# SX1308_GTW_e381v02c_SX1308_part.net
KiCad netlist of a schematic drawn in Altium Designer
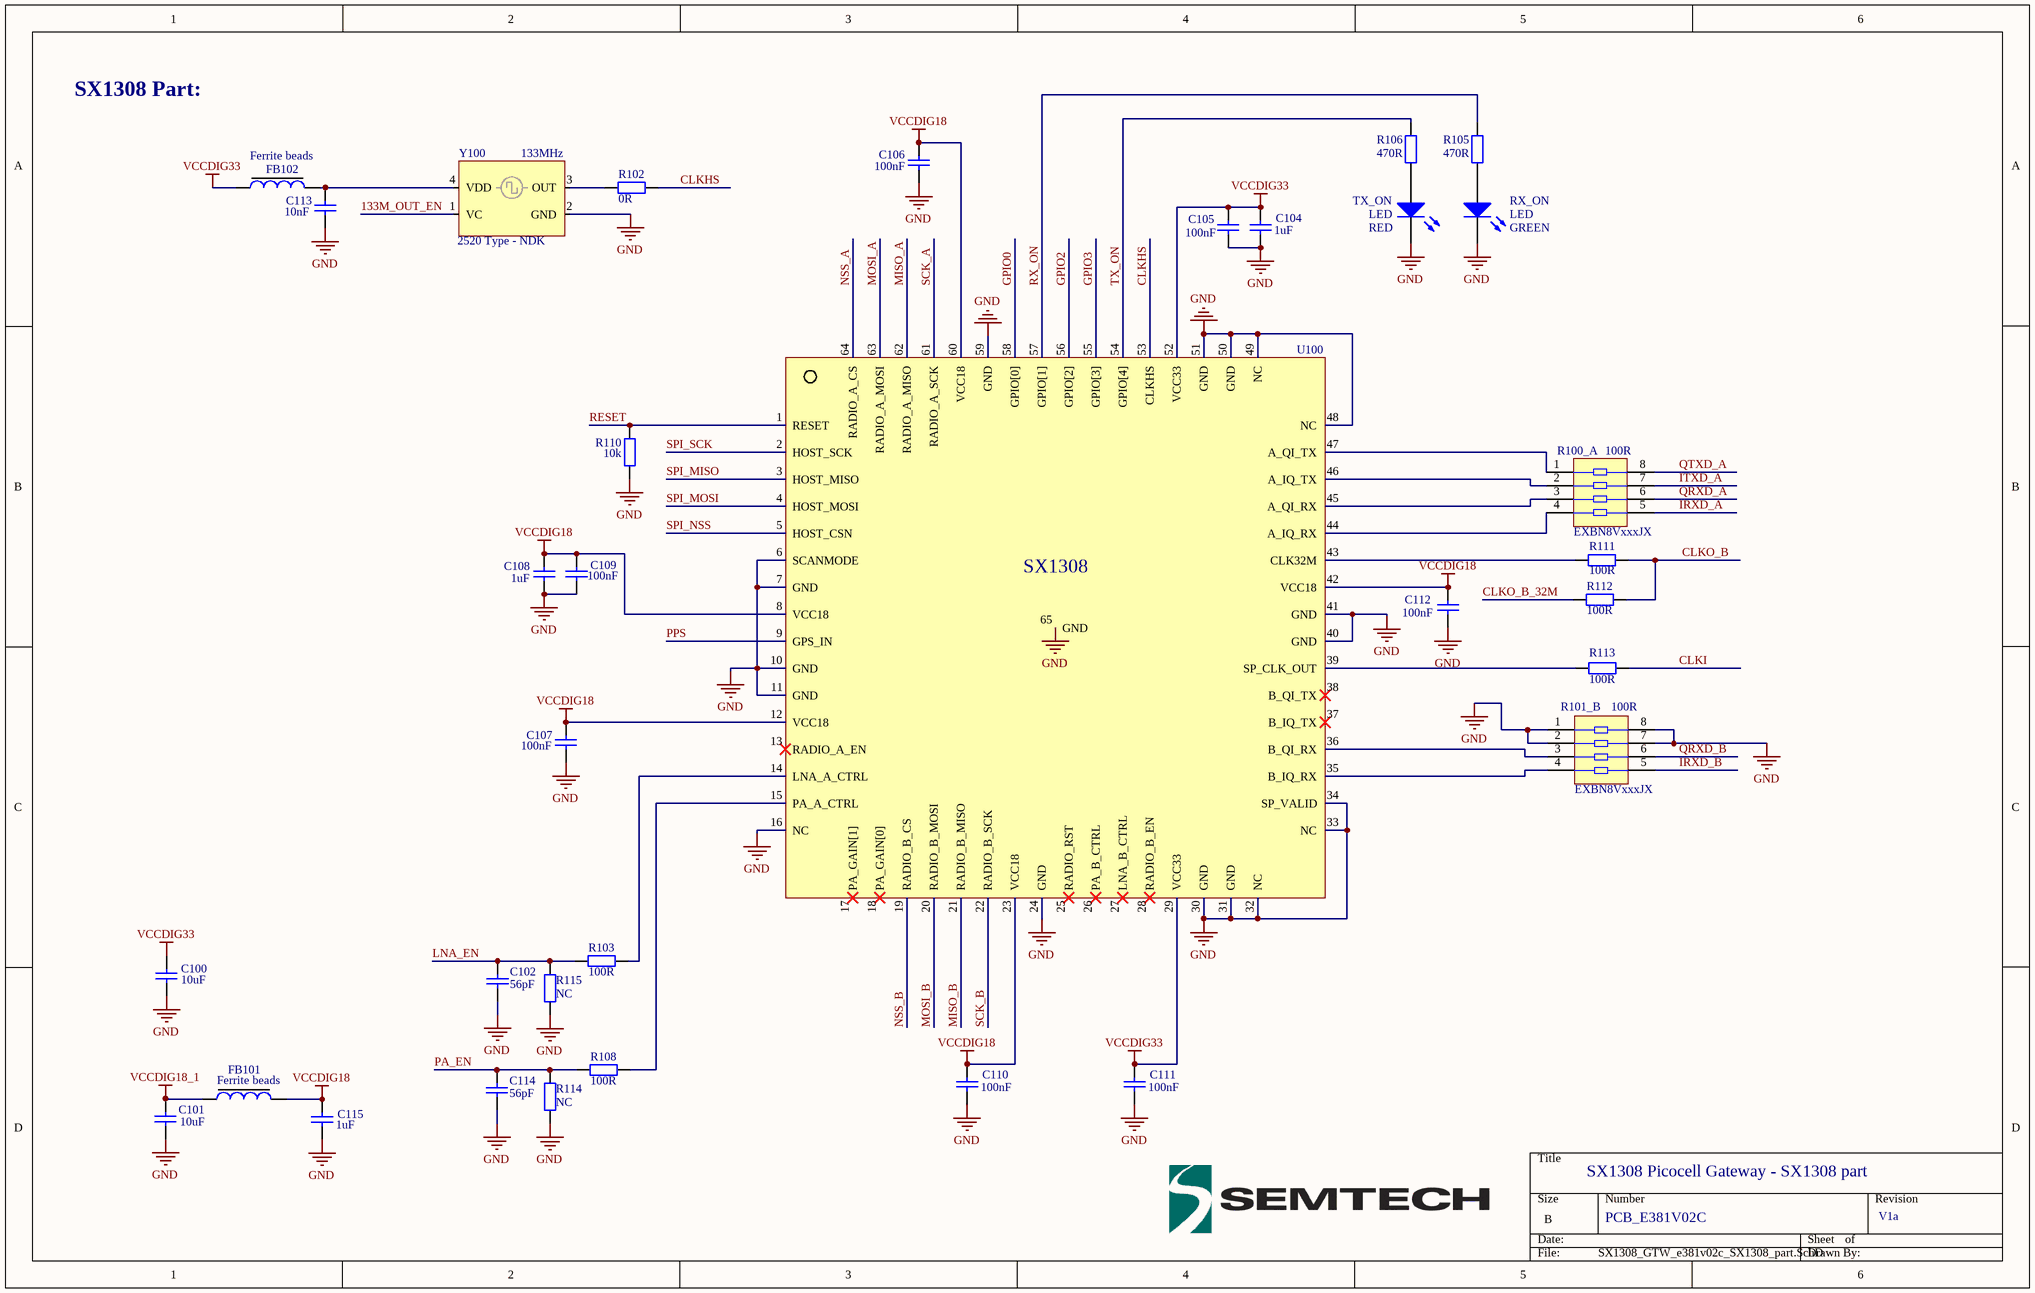
[diagram p0: SX1308_GTW_e381v02c_SX1308_part.SchDoc]

(export (version "E")
  (design (tool "Eeschema 10.0.6"))
  (components
    (comp (ref "C100")
      (value "10uF")
      (footprint "rlc_805_smd")
      (description "Capacitor SMD")
      (fields (field (name "Comment") "Cap") (field (name "PUBLISHER") "Altium Limited"))
      (libsource (lib "SX1308_GTW_e381v02c") (part "Cap"))
    )
    (comp (ref "C101")
      (value "10uF")
      (footprint "rlc_805_smd")
      (description "Capacitor SMD")
      (fields (field (name "Comment") "Cap") (field (name "PUBLISHER") "Altium Limited"))
      (libsource (lib "SX1308_GTW_e381v02c") (part "Cap"))
    )
    (comp (ref "C102")
      (value "56pF")
      (footprint "rlc_402_smd")
      (description "Capacitor SMD")
      (fields (field (name "Comment") "Cap") (field (name "PUBLISHER") "Altium Limited"))
      (libsource (lib "SX1308_GTW_e381v02c") (part "Cap"))
    )
    (comp (ref "C104")
      (value "1uF")
      (footprint "rlc_603_smd")
      (description "Capacitor SMD")
      (fields (field (name "Comment") "Cap") (field (name "PUBLISHER") "Altium Limited"))
      (libsource (lib "SX1308_GTW_e381v02c") (part "Cap"))
    )
    (comp (ref "C105")
      (value "100nF")
      (footprint "rlc_402_smd")
      (description "Capacitor SMD")
      (fields (field (name "Comment") "Cap") (field (name "PUBLISHER") "Altium Limited"))
      (libsource (lib "SX1308_GTW_e381v02c") (part "Cap"))
    )
    (comp (ref "C106")
      (value "100nF")
      (footprint "rlc_402_smd")
      (description "Capacitor SMD")
      (fields (field (name "Comment") "Cap") (field (name "PUBLISHER") "Altium Limited"))
      (libsource (lib "SX1308_GTW_e381v02c") (part "Cap"))
    )
    (comp (ref "C107")
      (value "100nF")
      (footprint "rlc_402_smd")
      (description "Capacitor SMD")
      (fields (field (name "Comment") "Cap") (field (name "PUBLISHER") "Altium Limited"))
      (libsource (lib "SX1308_GTW_e381v02c") (part "Cap"))
    )
    (comp (ref "C108")
      (value "1uF")
      (footprint "rlc_603_smd")
      (description "Capacitor SMD")
      (fields (field (name "Comment") "Cap") (field (name "PUBLISHER") "Altium Limited"))
      (libsource (lib "SX1308_GTW_e381v02c") (part "Cap"))
    )
    (comp (ref "C109")
      (value "100nF")
      (footprint "rlc_402_smd")
      (description "Capacitor SMD")
      (fields (field (name "Comment") "Cap") (field (name "PUBLISHER") "Altium Limited"))
      (libsource (lib "SX1308_GTW_e381v02c") (part "Cap"))
    )
    (comp (ref "C110")
      (value "100nF")
      (footprint "rlc_402_smd")
      (description "Capacitor SMD")
      (fields (field (name "Comment") "Cap") (field (name "PUBLISHER") "Altium Limited"))
      (libsource (lib "SX1308_GTW_e381v02c") (part "Cap"))
    )
    (comp (ref "C111")
      (value "100nF")
      (footprint "rlc_402_smd")
      (description "Capacitor SMD")
      (fields (field (name "Comment") "Cap") (field (name "PUBLISHER") "Altium Limited"))
      (libsource (lib "SX1308_GTW_e381v02c") (part "Cap"))
    )
    (comp (ref "C112")
      (value "100nF")
      (footprint "rlc_402_smd")
      (description "Capacitor SMD")
      (fields (field (name "Comment") "Cap") (field (name "PUBLISHER") "Altium Limited"))
      (libsource (lib "SX1308_GTW_e381v02c") (part "Cap"))
    )
    (comp (ref "C113")
      (value "10nF")
      (footprint "rlc_402_smd")
      (description "Capacitor SMD")
      (fields (field (name "Comment") "Cap") (field (name "PUBLISHER") "Altium Limited"))
      (libsource (lib "SX1308_GTW_e381v02c") (part "Cap"))
    )
    (comp (ref "C114")
      (value "56pF")
      (footprint "rlc_402_smd")
      (description "Capacitor SMD")
      (fields (field (name "Comment") "Cap") (field (name "PUBLISHER") "Altium Limited"))
      (libsource (lib "SX1308_GTW_e381v02c") (part "Cap"))
    )
    (comp (ref "C115")
      (value "1uF")
      (footprint "rlc_603_smd")
      (description "Capacitor SMD")
      (fields (field (name "Comment") "Cap") (field (name "PUBLISHER") "Altium Limited"))
      (libsource (lib "SX1308_GTW_e381v02c") (part "Cap"))
    )
    (comp (ref "FB101")
      (value "Ferrite beads")
      (footprint "rlc_402_smd")
      (libsource (lib "SX1308_GTW_e381v02c") (part "Ferrite beads"))
    )
    (comp (ref "FB102")
      (value "Ferrite beads")
      (footprint "rlc_402_smd")
      (libsource (lib "SX1308_GTW_e381v02c") (part "Ferrite beads"))
    )
    (comp (ref "R100_A")
      (value "EXBN8VxxxJX")
      (footprint "EXB28V")
      (description "Mini-Flat Package, Isolated Resistor Network, 0.031 W/resistor")
      (fields (field (name "ALTIUM_VALUE") "100R"))
      (libsource (lib "SX1308_GTW_e381v02c") (part "EXBN8VxxxJX"))
    )
    (comp (ref "R101_B")
      (value "EXBN8VxxxJX")
      (footprint "EXB28V")
      (description "Mini-Flat Package, Isolated Resistor Network, 0.031 W/resistor")
      (fields (field (name "ALTIUM_VALUE") "100R"))
      (libsource (lib "SX1308_GTW_e381v02c") (part "EXBN8VxxxJX"))
    )
    (comp (ref "R102")
      (value "0R")
      (footprint "rlc_402_smd")
      (description "Resistor SMD - IEC symbol version")
      (fields (field (name "Comment") "Resistor"))
      (libsource (lib "SX1308_GTW_e381v02c") (part "Resistor"))
    )
    (comp (ref "R103")
      (value "100R")
      (footprint "rlc_402_smd")
      (description "Resistor SMD - IEC symbol version")
      (fields (field (name "Comment") "Resistor"))
      (libsource (lib "SX1308_GTW_e381v02c") (part "Resistor"))
    )
    (comp (ref "R105")
      (value "470R")
      (footprint "rlc_402_smd")
      (description "Resistor SMD - IEC symbol version")
      (fields (field (name "Comment") "Resistor"))
      (libsource (lib "") (part "Resistor_2"))
    )
    (comp (ref "R106")
      (value "470R")
      (footprint "rlc_402_smd")
      (description "Resistor SMD - IEC symbol version")
      (fields (field (name "Comment") "Resistor"))
      (libsource (lib "") (part "Resistor_2"))
    )
    (comp (ref "R108")
      (value "100R")
      (footprint "rlc_402_smd")
      (description "Resistor SMD - IEC symbol version")
      (fields (field (name "Comment") "Resistor"))
      (libsource (lib "SX1308_GTW_e381v02c") (part "Resistor"))
    )
    (comp (ref "R110")
      (value "10k")
      (footprint "rlc_402_smd")
      (description "Resistor SMD - IEC symbol version")
      (fields (field (name "Comment") "Resistor"))
      (libsource (lib "") (part "Resistor_2"))
    )
    (comp (ref "R111")
      (value "100R")
      (footprint "rlc_402_smd")
      (description "Resistor SMD - IEC symbol version")
      (fields (field (name "Comment") "Resistor"))
      (libsource (lib "") (part "Resistor_1"))
    )
    (comp (ref "R112")
      (value "100R")
      (footprint "rlc_402_smd")
      (description "Resistor SMD - IEC symbol version")
      (fields (field (name "Comment") "Resistor"))
      (libsource (lib "") (part "Resistor_1"))
    )
    (comp (ref "R113")
      (value "100R")
      (footprint "rlc_402_smd")
      (description "Resistor SMD - IEC symbol version")
      (fields (field (name "Comment") "Resistor"))
      (libsource (lib "") (part "Resistor_1"))
    )
    (comp (ref "R114")
      (value "NC")
      (footprint "rlc_402_smd")
      (description "Resistor SMD - IEC symbol version")
      (fields (field (name "Comment") "Resistor"))
      (libsource (lib "") (part "Resistor_3"))
    )
    (comp (ref "R115")
      (value "NC")
      (footprint "rlc_402_smd")
      (description "Resistor SMD - IEC symbol version")
      (fields (field (name "Comment") "Resistor"))
      (libsource (lib "") (part "Resistor_3"))
    )
    (comp (ref "RX_ON")
      (value "LED")
      (footprint "CD3224")
      (fields (field (name "TYPE") "GREEN"))
      (libsource (lib "SX1308_GTW_e381v02c") (part "LED"))
    )
    (comp (ref "TX_ON")
      (value "LED")
      (footprint "CD3224")
      (fields (field (name "TYPE") "RED"))
      (libsource (lib "SX1308_GTW_e381v02c") (part "LED"))
    )
    (comp (ref "U100")
      (value "SX1308")
      (footprint "vqfn64_9x9mm")
      (libsource (lib "SX1308_GTW_e381v02c") (part "SX1301"))
    )
    (comp (ref "Y100")
      (value "2520 Type - NDK")
      (footprint "TCXO 2.5x2.0mm")
      (description "VCTCXO")
      (fields (field (name "ALTIUM_VALUE") "133MHz"))
      (libsource (lib "SX1308_GTW_e381v02c") (part "VCTCXO"))
    )
  )
  (nets
    (net (code "1") (name "/133M_OUT_EN") (class "Default")
      (node (ref "Y100") (pin "1") (pinfunction "VC_1") (pintype "passive"))
    )
    (net (code "2") (name "/CLKHS") (class "Default")
      (node (ref "R102") (pin "1") (pinfunction "1_1") (pintype "passive"))
      (node (ref "U100") (pin "53") (pinfunction "CLKHS_53") (pintype "passive"))
    )
    (net (code "3") (name "/CLKI") (class "Default")
      (node (ref "R113") (pin "2") (pinfunction "2_2") (pintype "passive"))
    )
    (net (code "4") (name "/CLKO_B") (class "Default")
      (node (ref "R111") (pin "2") (pinfunction "2_2") (pintype "passive"))
      (node (ref "R112") (pin "2") (pinfunction "2_2") (pintype "passive"))
    )
    (net (code "5") (name "/CLKO_B_32M") (class "Default")
      (node (ref "R112") (pin "1") (pinfunction "1_1") (pintype "passive"))
    )
    (net (code "6") (name "/GPIO0") (class "Default")
      (node (ref "U100") (pin "58") (pinfunction "GPIO[0]_58") (pintype "passive"))
    )
    (net (code "7") (name "/GPIO2") (class "Default")
      (node (ref "U100") (pin "56") (pinfunction "GPIO[2]_56") (pintype "passive"))
    )
    (net (code "8") (name "/GPIO3") (class "Default")
      (node (ref "U100") (pin "55") (pinfunction "GPIO[3]_55") (pintype "passive"))
    )
    (net (code "9") (name "/IRXD_A") (class "Default")
      (node (ref "R100_A") (pin "5") (pinfunction "5_5") (pintype "passive"))
    )
    (net (code "10") (name "/IRXD_B") (class "Default")
      (node (ref "R101_B") (pin "5") (pinfunction "5_5") (pintype "passive"))
    )
    (net (code "11") (name "/ITXD_A") (class "Default")
      (node (ref "R100_A") (pin "7") (pinfunction "7_7") (pintype "passive"))
    )
    (net (code "12") (name "/LNA_EN") (class "Default")
      (node (ref "C102") (pin "2") (pinfunction "2_2") (pintype "passive"))
      (node (ref "R103") (pin "2") (pinfunction "2_2") (pintype "passive"))
      (node (ref "R115") (pin "1") (pinfunction "1_1") (pintype "passive"))
    )
    (net (code "13") (name "/MISO_A") (class "Default")
      (node (ref "U100") (pin "62") (pinfunction "RADIO_A_MISO_62") (pintype "passive"))
    )
    (net (code "14") (name "/MISO_B") (class "Default")
      (node (ref "U100") (pin "21") (pinfunction "RADIO_B_MISO_21") (pintype "passive"))
    )
    (net (code "15") (name "/MOSI_A") (class "Default")
      (node (ref "U100") (pin "63") (pinfunction "RADIO_A_MOSI_63") (pintype "passive"))
    )
    (net (code "16") (name "/MOSI_B") (class "Default")
      (node (ref "U100") (pin "20") (pinfunction "RADIO_B_MOSI_20") (pintype "passive"))
    )
    (net (code "17") (name "/NSS_A") (class "Default")
      (node (ref "U100") (pin "64") (pinfunction "RADIO_A_CS_64") (pintype "passive"))
    )
    (net (code "18") (name "/NSS_B") (class "Default")
      (node (ref "U100") (pin "19") (pinfunction "RADIO_B_CS_19") (pintype "passive"))
    )
    (net (code "19") (name "/PA_EN") (class "Default")
      (node (ref "C114") (pin "2") (pinfunction "2_2") (pintype "passive"))
      (node (ref "R108") (pin "2") (pinfunction "2_2") (pintype "passive"))
      (node (ref "R114") (pin "1") (pinfunction "1_1") (pintype "passive"))
    )
    (net (code "20") (name "/PPS") (class "Default")
      (node (ref "U100") (pin "9") (pinfunction "GPS_IN_9") (pintype "passive"))
    )
    (net (code "21") (name "/QRXD_A") (class "Default")
      (node (ref "R100_A") (pin "6") (pinfunction "6_6") (pintype "passive"))
    )
    (net (code "22") (name "/QRXD_B") (class "Default")
      (node (ref "R101_B") (pin "6") (pinfunction "6_6") (pintype "passive"))
    )
    (net (code "23") (name "/QTXD_A") (class "Default")
      (node (ref "R100_A") (pin "8") (pinfunction "8_8") (pintype "passive"))
    )
    (net (code "24") (name "/RESET") (class "Default")
      (node (ref "R110") (pin "2") (pinfunction "2_2") (pintype "passive"))
      (node (ref "U100") (pin "1") (pinfunction "RESET_1") (pintype "passive"))
    )
    (net (code "25") (name "/RX_ON") (class "Default")
      (node (ref "R105") (pin "2") (pinfunction "2_2") (pintype "passive"))
      (node (ref "U100") (pin "57") (pinfunction "GPIO[1]_57") (pintype "passive"))
    )
    (net (code "26") (name "/SCK_A") (class "Default")
      (node (ref "U100") (pin "61") (pinfunction "RADIO_A_SCK_61") (pintype "passive"))
    )
    (net (code "27") (name "/SCK_B") (class "Default")
      (node (ref "U100") (pin "22") (pinfunction "RADIO_B_SCK_22") (pintype "passive"))
    )
    (net (code "28") (name "/SPI_MISO") (class "Default")
      (node (ref "U100") (pin "3") (pinfunction "HOST_MISO_3") (pintype "passive"))
    )
    (net (code "29") (name "/SPI_MOSI") (class "Default")
      (node (ref "U100") (pin "4") (pinfunction "HOST_MOSI_4") (pintype "passive"))
    )
    (net (code "30") (name "/SPI_NSS") (class "Default")
      (node (ref "U100") (pin "5") (pinfunction "HOST_CSN_5") (pintype "passive"))
    )
    (net (code "31") (name "/SPI_SCK") (class "Default")
      (node (ref "U100") (pin "2") (pinfunction "HOST_SCK_2") (pintype "passive"))
    )
    (net (code "32") (name "/TX_ON") (class "Default")
      (node (ref "R106") (pin "2") (pinfunction "2_2") (pintype "passive"))
      (node (ref "U100") (pin "54") (pinfunction "GPIO[4]_54") (pintype "passive"))
    )
    (net (code "33") (name "GND") (class "Default")
      (node (ref "C100") (pin "1") (pinfunction "1_1") (pintype "passive"))
      (node (ref "C101") (pin "1") (pinfunction "1_1") (pintype "passive"))
      (node (ref "C102") (pin "1") (pinfunction "1_1") (pintype "passive"))
      (node (ref "C104") (pin "1") (pinfunction "1_1") (pintype "passive"))
      (node (ref "C105") (pin "1") (pinfunction "1_1") (pintype "passive"))
      (node (ref "C106") (pin "1") (pinfunction "1_1") (pintype "passive"))
      (node (ref "C107") (pin "1") (pinfunction "1_1") (pintype "passive"))
      (node (ref "C108") (pin "1") (pinfunction "1_1") (pintype "passive"))
      (node (ref "C109") (pin "1") (pinfunction "1_1") (pintype "passive"))
      (node (ref "C110") (pin "1") (pinfunction "1_1") (pintype "passive"))
      (node (ref "C111") (pin "1") (pinfunction "1_1") (pintype "passive"))
      (node (ref "C112") (pin "1") (pinfunction "1_1") (pintype "passive"))
      (node (ref "C113") (pin "1") (pinfunction "1_1") (pintype "passive"))
      (node (ref "C114") (pin "1") (pinfunction "1_1") (pintype "passive"))
      (node (ref "C115") (pin "2") (pinfunction "2_2") (pintype "passive"))
      (node (ref "R101_B") (pin "1") (pinfunction "1_1") (pintype "passive"))
      (node (ref "R101_B") (pin "2") (pinfunction "2_2") (pintype "passive"))
      (node (ref "R101_B") (pin "7") (pinfunction "7_7") (pintype "passive"))
      (node (ref "R101_B") (pin "8") (pinfunction "8_8") (pintype "passive"))
      (node (ref "R110") (pin "1") (pinfunction "1_1") (pintype "passive"))
      (node (ref "R114") (pin "2") (pinfunction "2_2") (pintype "passive"))
      (node (ref "R115") (pin "2") (pinfunction "2_2") (pintype "passive"))
      (node (ref "RX_ON") (pin "2") (pinfunction "K_2") (pintype "passive"))
      (node (ref "TX_ON") (pin "2") (pinfunction "K_2") (pintype "passive"))
      (node (ref "U100") (pin "10") (pinfunction "GND_10") (pintype "passive"))
      (node (ref "U100") (pin "11") (pinfunction "GND_11") (pintype "passive"))
      (node (ref "U100") (pin "16") (pinfunction "NC_16") (pintype "passive"))
      (node (ref "U100") (pin "24") (pinfunction "GND_24") (pintype "passive"))
      (node (ref "U100") (pin "30") (pinfunction "GND_30") (pintype "passive"))
      (node (ref "U100") (pin "31") (pinfunction "GND_31") (pintype "passive"))
      (node (ref "U100") (pin "32") (pinfunction "NC_32") (pintype "passive"))
      (node (ref "U100") (pin "33") (pinfunction "NC_33") (pintype "passive"))
      (node (ref "U100") (pin "34") (pinfunction "SP_VALID_34") (pintype "passive"))
      (node (ref "U100") (pin "40") (pinfunction "GND_40") (pintype "passive"))
      (node (ref "U100") (pin "41") (pinfunction "GND_41") (pintype "passive"))
      (node (ref "U100") (pin "48") (pinfunction "NC_48") (pintype "passive"))
      (node (ref "U100") (pin "49") (pinfunction "NC_49") (pintype "passive"))
      (node (ref "U100") (pin "50") (pinfunction "GND_50") (pintype "passive"))
      (node (ref "U100") (pin "51") (pinfunction "GND_51") (pintype "passive"))
      (node (ref "U100") (pin "59") (pinfunction "GND_59") (pintype "passive"))
      (node (ref "U100") (pin "6") (pinfunction "SCANMODE_6") (pintype "passive"))
      (node (ref "U100") (pin "65") (pinfunction "GND_65") (pintype "passive"))
      (node (ref "U100") (pin "7") (pinfunction "GND_7") (pintype "passive"))
      (node (ref "Y100") (pin "2") (pinfunction "GND_2") (pintype "passive"))
    )
    (net (code "34") (name "Net-(RX_ON-A)") (class "Default")
      (node (ref "R105") (pin "1") (pinfunction "1_1") (pintype "passive"))
      (node (ref "RX_ON") (pin "1") (pinfunction "A_1") (pintype "passive"))
    )
    (net (code "35") (name "Net-(TX_ON-A)") (class "Default")
      (node (ref "R106") (pin "1") (pinfunction "1_1") (pintype "passive"))
      (node (ref "TX_ON") (pin "1") (pinfunction "A_1") (pintype "passive"))
    )
    (net (code "36") (name "Net-(U100-A_IQ_RX)") (class "Default")
      (node (ref "R100_A") (pin "4") (pinfunction "4_4") (pintype "passive"))
      (node (ref "U100") (pin "44") (pinfunction "A_IQ_RX_44") (pintype "passive"))
    )
    (net (code "37") (name "Net-(U100-A_IQ_TX)") (class "Default")
      (node (ref "R100_A") (pin "2") (pinfunction "2_2") (pintype "passive"))
      (node (ref "U100") (pin "46") (pinfunction "A_IQ_TX_46") (pintype "passive"))
    )
    (net (code "38") (name "Net-(U100-A_QI_RX)") (class "Default")
      (node (ref "R100_A") (pin "3") (pinfunction "3_3") (pintype "passive"))
      (node (ref "U100") (pin "45") (pinfunction "A_QI_RX_45") (pintype "passive"))
    )
    (net (code "39") (name "Net-(U100-A_QI_TX)") (class "Default")
      (node (ref "R100_A") (pin "1") (pinfunction "1_1") (pintype "passive"))
      (node (ref "U100") (pin "47") (pinfunction "A_QI_TX_47") (pintype "passive"))
    )
    (net (code "40") (name "Net-(U100-B_IQ_RX)") (class "Default")
      (node (ref "R101_B") (pin "4") (pinfunction "4_4") (pintype "passive"))
      (node (ref "U100") (pin "35") (pinfunction "B_IQ_RX_35") (pintype "passive"))
    )
    (net (code "41") (name "Net-(U100-B_QI_RX)") (class "Default")
      (node (ref "R101_B") (pin "3") (pinfunction "3_3") (pintype "passive"))
      (node (ref "U100") (pin "36") (pinfunction "B_QI_RX_36") (pintype "passive"))
    )
    (net (code "42") (name "Net-(U100-CLK32M)") (class "Default")
      (node (ref "R111") (pin "1") (pinfunction "1_1") (pintype "passive"))
      (node (ref "U100") (pin "43") (pinfunction "CLK32M_43") (pintype "passive"))
    )
    (net (code "43") (name "Net-(U100-LNA_A_CTRL)") (class "Default")
      (node (ref "R103") (pin "1") (pinfunction "1_1") (pintype "passive"))
      (node (ref "U100") (pin "14") (pinfunction "LNA_A_CTRL_14") (pintype "passive"))
    )
    (net (code "44") (name "Net-(U100-PA_A_CTRL)") (class "Default")
      (node (ref "R108") (pin "1") (pinfunction "1_1") (pintype "passive"))
      (node (ref "U100") (pin "15") (pinfunction "PA_A_CTRL_15") (pintype "passive"))
    )
    (net (code "45") (name "Net-(U100-SP_CLK_OUT)") (class "Default")
      (node (ref "R113") (pin "1") (pinfunction "1_1") (pintype "passive"))
      (node (ref "U100") (pin "39") (pinfunction "SP_CLK_OUT_39") (pintype "passive"))
    )
    (net (code "46") (name "Net-(Y100-OUT)") (class "Default")
      (node (ref "R102") (pin "2") (pinfunction "2_2") (pintype "passive"))
      (node (ref "Y100") (pin "3") (pinfunction "OUT_3") (pintype "passive"))
    )
    (net (code "47") (name "Net-(Y100-VDD)") (class "Default")
      (node (ref "C113") (pin "2") (pinfunction "2_2") (pintype "passive"))
      (node (ref "FB102") (pin "2") (pinfunction "2_2") (pintype "passive"))
      (node (ref "Y100") (pin "4") (pinfunction "VDD_4") (pintype "passive"))
    )
    (net (code "48") (name "VCCDIG18") (class "Default")
      (node (ref "C106") (pin "2") (pinfunction "2_2") (pintype "passive"))
      (node (ref "C107") (pin "2") (pinfunction "2_2") (pintype "passive"))
      (node (ref "C108") (pin "2") (pinfunction "2_2") (pintype "passive"))
      (node (ref "C109") (pin "2") (pinfunction "2_2") (pintype "passive"))
      (node (ref "C110") (pin "2") (pinfunction "2_2") (pintype "passive"))
      (node (ref "C112") (pin "2") (pinfunction "2_2") (pintype "passive"))
      (node (ref "C115") (pin "1") (pinfunction "1_1") (pintype "passive"))
      (node (ref "FB101") (pin "2") (pinfunction "2_2") (pintype "passive"))
      (node (ref "U100") (pin "12") (pinfunction "VCC18_12") (pintype "passive"))
      (node (ref "U100") (pin "23") (pinfunction "VCC18_23") (pintype "passive"))
      (node (ref "U100") (pin "42") (pinfunction "VCC18_42") (pintype "passive"))
      (node (ref "U100") (pin "60") (pinfunction "VCC18_60") (pintype "passive"))
      (node (ref "U100") (pin "8") (pinfunction "VCC18_8") (pintype "passive"))
    )
    (net (code "49") (name "VCCDIG18_1") (class "Default")
      (node (ref "C101") (pin "2") (pinfunction "2_2") (pintype "passive"))
      (node (ref "FB101") (pin "1") (pinfunction "1_1") (pintype "passive"))
    )
    (net (code "50") (name "VCCDIG33") (class "Default")
      (node (ref "C100") (pin "2") (pinfunction "2_2") (pintype "passive"))
      (node (ref "C104") (pin "2") (pinfunction "2_2") (pintype "passive"))
      (node (ref "C105") (pin "2") (pinfunction "2_2") (pintype "passive"))
      (node (ref "C111") (pin "2") (pinfunction "2_2") (pintype "passive"))
      (node (ref "FB102") (pin "1") (pinfunction "1_1") (pintype "passive"))
      (node (ref "U100") (pin "29") (pinfunction "VCC33_29") (pintype "passive"))
      (node (ref "U100") (pin "52") (pinfunction "VCC33_52") (pintype "passive"))
    )
    (net (code "51") (name "unconnected-(U100-B_IQ_TX-Pad37)") (class "Default")
      (node (ref "U100") (pin "37") (pinfunction "B_IQ_TX_37") (pintype "passive+no_connect"))
    )
    (net (code "52") (name "unconnected-(U100-B_QI_TX-Pad38)") (class "Default")
      (node (ref "U100") (pin "38") (pinfunction "B_QI_TX_38") (pintype "passive+no_connect"))
    )
    (net (code "53") (name "unconnected-(U100-LNA_B_CTRL-Pad27)") (class "Default")
      (node (ref "U100") (pin "27") (pinfunction "LNA_B_CTRL_27") (pintype "passive+no_connect"))
    )
    (net (code "54") (name "unconnected-(U100-PA_B_CTRL-Pad26)") (class "Default")
      (node (ref "U100") (pin "26") (pinfunction "PA_B_CTRL_26") (pintype "passive+no_connect"))
    )
    (net (code "55") (name "unconnected-(U100-PA_GAIN[0]-Pad18)") (class "Default")
      (node (ref "U100") (pin "18") (pinfunction "PA_GAIN[0]_18") (pintype "passive+no_connect"))
    )
    (net (code "56") (name "unconnected-(U100-PA_GAIN[1]-Pad17)") (class "Default")
      (node (ref "U100") (pin "17") (pinfunction "PA_GAIN[1]_17") (pintype "passive+no_connect"))
    )
    (net (code "57") (name "unconnected-(U100-RADIO_A_EN-Pad13)") (class "Default")
      (node (ref "U100") (pin "13") (pinfunction "RADIO_A_EN_13") (pintype "passive+no_connect"))
    )
    (net (code "58") (name "unconnected-(U100-RADIO_B_EN-Pad28)") (class "Default")
      (node (ref "U100") (pin "28") (pinfunction "RADIO_B_EN_28") (pintype "passive+no_connect"))
    )
    (net (code "59") (name "unconnected-(U100-RADIO_RST-Pad25)") (class "Default")
      (node (ref "U100") (pin "25") (pinfunction "RADIO_RST_25") (pintype "passive+no_connect"))
    )
  )
)
